# Sheet2.net
KiCad netlist of a schematic drawn in Altium Designer
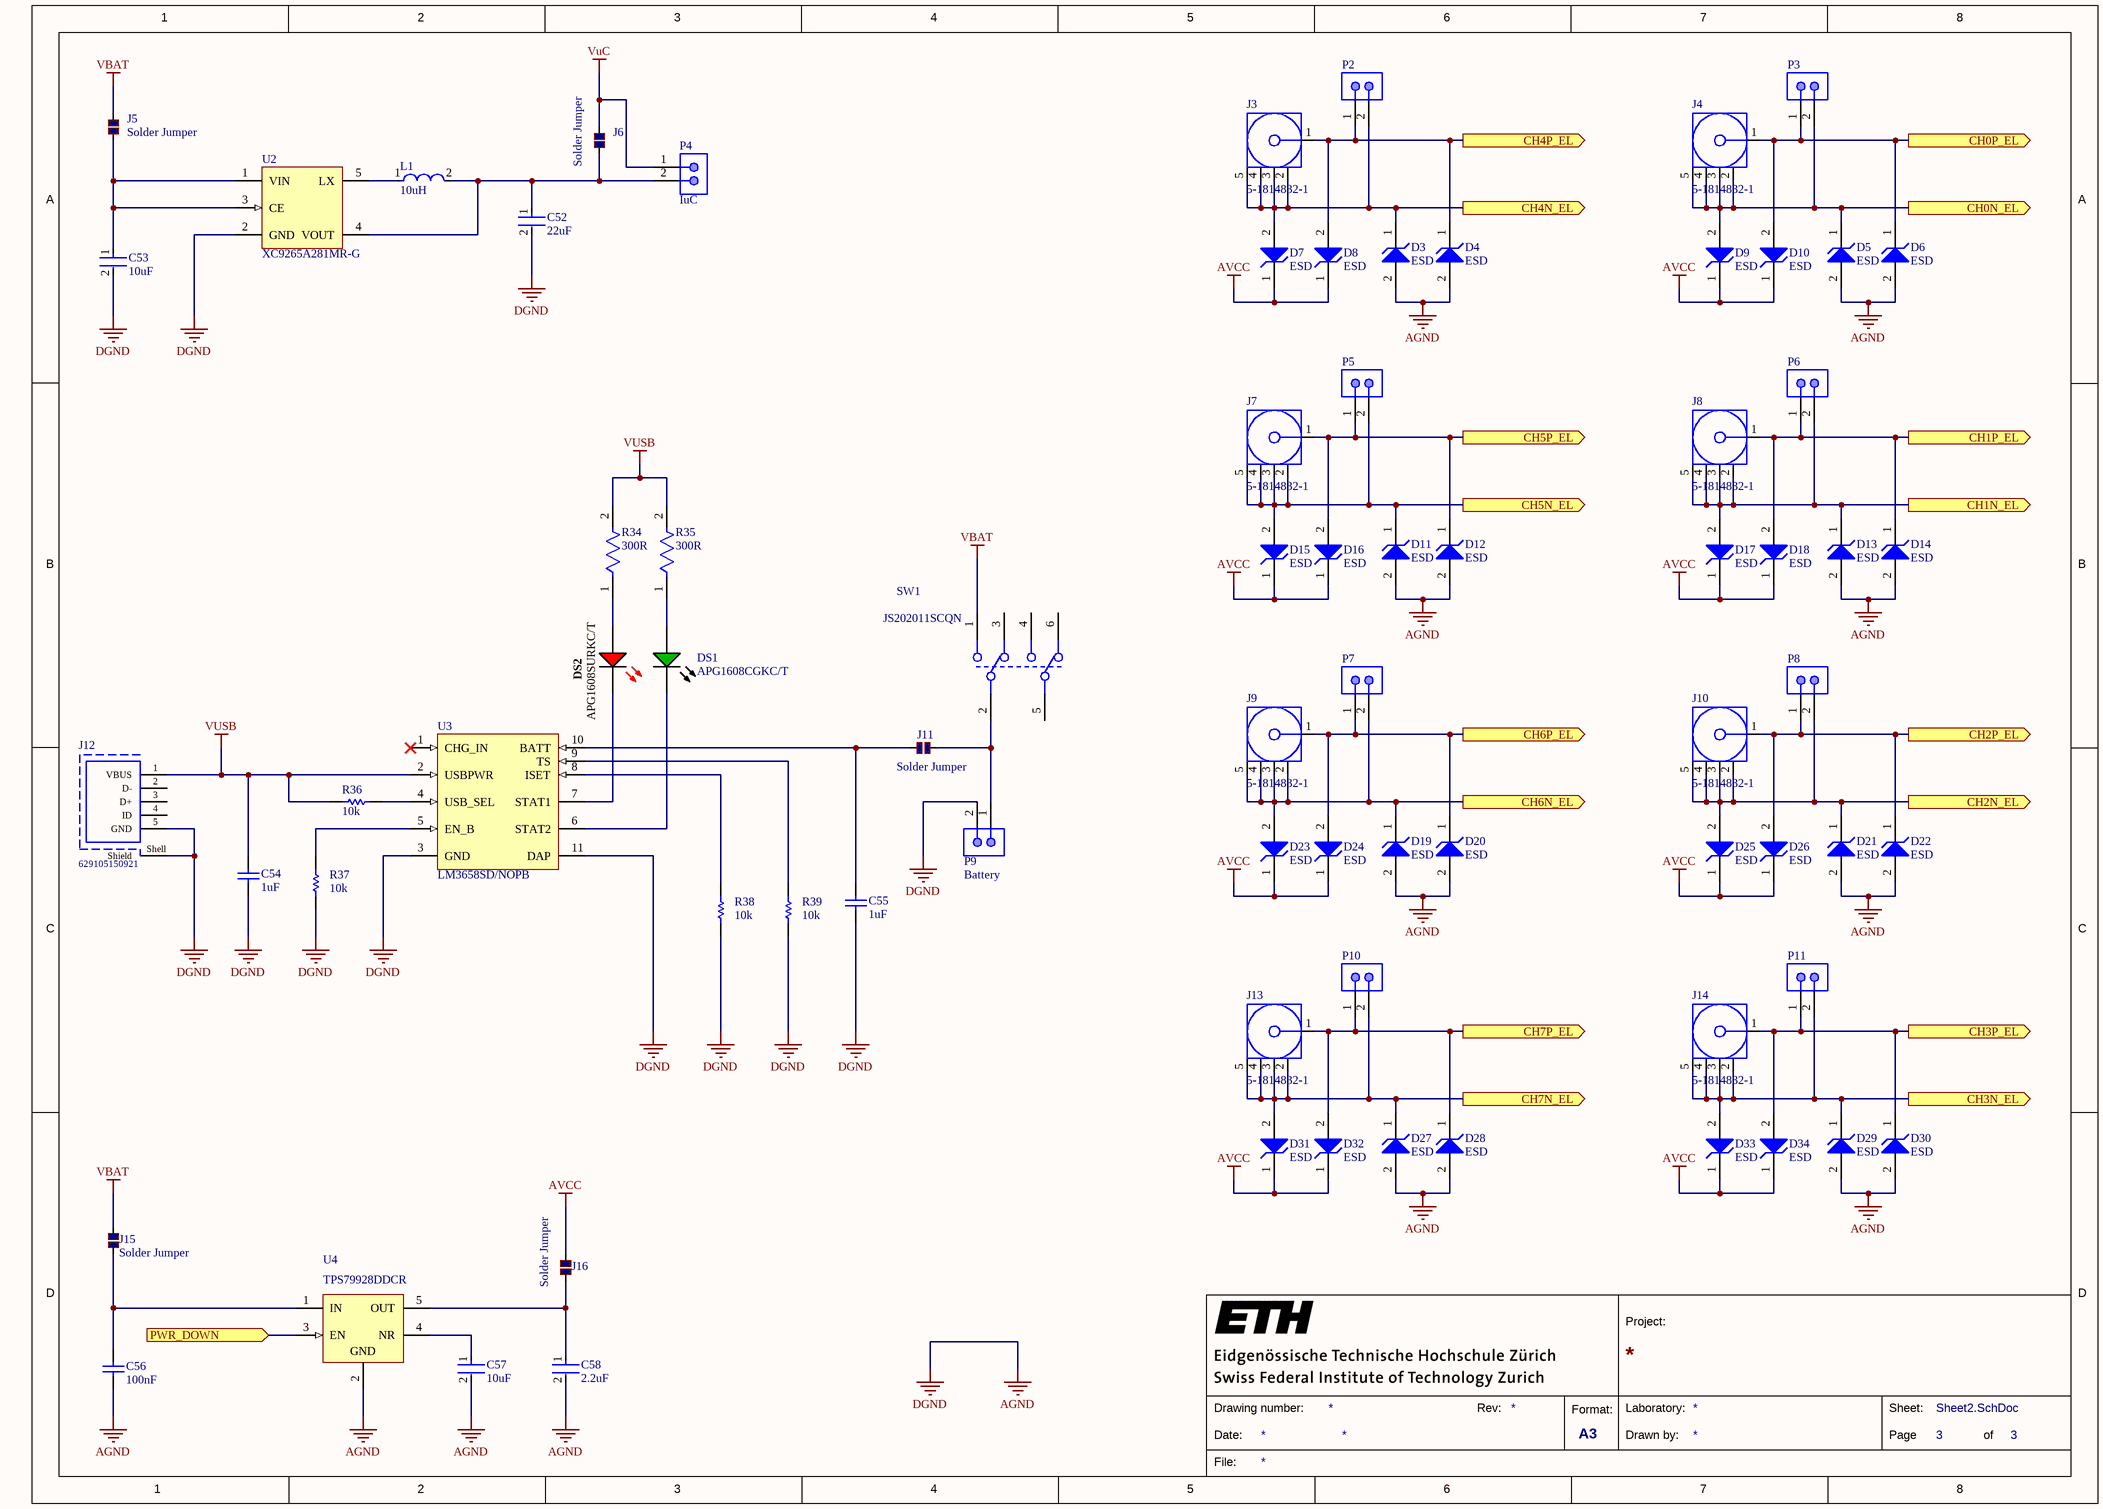
[diagram p0: Sheet2.SchDoc]

(export (version "E")
  (design (tool "Eeschema 10.0.6"))
  (components
    (comp (ref "C52")
      (value "22uF")
      (footprint "FP-CL10-IPC_A")
      (description "Cap Ceramic 22uF 6.3V X5R ±20% Pad SMD 0603 +85°C T/R")
      (fields (field (name "TOLERANCE") "20%"))
      (libsource (lib "Altium Content Vault") (part "b4654b650e69147ec39a6b967a45e02"))
    )
    (comp (ref "C53")
      (value "10uF")
      (footprint "FP-GRM188-0_1-e0_2_0_55-IPC_B")
      (description "Chip Multilayer Ceramic Capacitors for General Purpose, 0603, 10uF, X5R, 15%, 20%, 4V")
      (fields (field (name "TOLERANCE") "20%") (field (name "VOLTAGE") "4V"))
      (libsource (lib "Altium Content Vault") (part "02cd4be3c70576c341d710602a673aa"))
    )
    (comp (ref "C54")
      (value "1uF")
      (footprint "CAPC1608X95X40ML15T15")
      (fields (field (name "MANUFACTURER") "Vitramon") (field (name "PART NUMBER") "VJ0603V105ZXQCW1BC"))
      (libsource (lib "Altium Content Vault") (part "CAP"))
    )
    (comp (ref "C55")
      (value "1uF")
      (footprint "CAPC1608X95X40ML15T15")
      (fields (field (name "MANUFACTURER") "Vitramon") (field (name "PART NUMBER") "VJ0603V105ZXQCW1BC"))
      (libsource (lib "Altium Content Vault") (part "CAP"))
    )
    (comp (ref "C56")
      (value "100nF")
      (footprint "CAPC1608X92X38LL15T08")
      (fields (field (name "MANUFACTURER") "Vitramon") (field (name "PART NUMBER") "VJ0603Y104JXJAC"))
      (libsource (lib "Altium Content Vault") (part "CAP"))
    )
    (comp (ref "C57")
      (value "10uF")
      (footprint "FP-GRM188-0_1-e0_2_0_55-IPC_B")
      (description "Chip Multilayer Ceramic Capacitors for General Purpose, 0603, 10uF, X5R, 15%, 20%, 4V")
      (fields (field (name "TOLERANCE") "20%") (field (name "VOLTAGE") "4V"))
      (libsource (lib "Altium Content Vault") (part "02cd4be3c70576c341d710602a673aa"))
    )
    (comp (ref "C58")
      (value "2.2uF")
      (footprint "FP-GRM188-0_1-e0_2_0_5-IPC_C")
      (description "Chip Multilayer Ceramic Capacitors for General Purpose, 0603, 2.2uF, X5R, 15%, 10%, 35V")
      (fields (field (name "VOLTAGE") "35V") (field (name "TOLERANCE") "10%"))
      (libsource (lib "Altium Content Vault") (part "11868f565c42a9108669ba33697ecf6"))
    )
    (comp (ref "D3")
      (value "ESD")
      (footprint "DFN110P160X55-2N")
      (description "TVS DIODE 5V 10.9V 2DFN")
      (libsource (lib "ETHZ Vault") (part "TVS DIODE"))
    )
    (comp (ref "D4")
      (value "ESD")
      (footprint "DFN110P160X55-2N")
      (description "TVS DIODE 5V 10.9V 2DFN")
      (libsource (lib "ETHZ Vault") (part "TVS DIODE"))
    )
    (comp (ref "D5")
      (value "ESD")
      (footprint "DFN110P160X55-2N")
      (description "TVS DIODE 5V 10.9V 2DFN")
      (libsource (lib "ETHZ Vault") (part "TVS DIODE"))
    )
    (comp (ref "D6")
      (value "ESD")
      (footprint "DFN110P160X55-2N")
      (description "TVS DIODE 5V 10.9V 2DFN")
      (libsource (lib "ETHZ Vault") (part "TVS DIODE"))
    )
    (comp (ref "D7")
      (value "ESD")
      (footprint "DFN110P160X55-2N")
      (description "TVS DIODE 5V 10.9V 2DFN")
      (libsource (lib "ETHZ Vault") (part "TVS DIODE"))
    )
    (comp (ref "D8")
      (value "ESD")
      (footprint "DFN110P160X55-2N")
      (description "TVS DIODE 5V 10.9V 2DFN")
      (libsource (lib "ETHZ Vault") (part "TVS DIODE"))
    )
    (comp (ref "D9")
      (value "ESD")
      (footprint "DFN110P160X55-2N")
      (description "TVS DIODE 5V 10.9V 2DFN")
      (libsource (lib "ETHZ Vault") (part "TVS DIODE"))
    )
    (comp (ref "D10")
      (value "ESD")
      (footprint "DFN110P160X55-2N")
      (description "TVS DIODE 5V 10.9V 2DFN")
      (libsource (lib "ETHZ Vault") (part "TVS DIODE"))
    )
    (comp (ref "D11")
      (value "ESD")
      (footprint "DFN110P160X55-2N")
      (description "TVS DIODE 5V 10.9V 2DFN")
      (libsource (lib "ETHZ Vault") (part "TVS DIODE"))
    )
    (comp (ref "D12")
      (value "ESD")
      (footprint "DFN110P160X55-2N")
      (description "TVS DIODE 5V 10.9V 2DFN")
      (libsource (lib "ETHZ Vault") (part "TVS DIODE"))
    )
    (comp (ref "D13")
      (value "ESD")
      (footprint "DFN110P160X55-2N")
      (description "TVS DIODE 5V 10.9V 2DFN")
      (libsource (lib "ETHZ Vault") (part "TVS DIODE"))
    )
    (comp (ref "D14")
      (value "ESD")
      (footprint "DFN110P160X55-2N")
      (description "TVS DIODE 5V 10.9V 2DFN")
      (libsource (lib "ETHZ Vault") (part "TVS DIODE"))
    )
    (comp (ref "D15")
      (value "ESD")
      (footprint "DFN110P160X55-2N")
      (description "TVS DIODE 5V 10.9V 2DFN")
      (libsource (lib "ETHZ Vault") (part "TVS DIODE"))
    )
    (comp (ref "D16")
      (value "ESD")
      (footprint "DFN110P160X55-2N")
      (description "TVS DIODE 5V 10.9V 2DFN")
      (libsource (lib "ETHZ Vault") (part "TVS DIODE"))
    )
    (comp (ref "D17")
      (value "ESD")
      (footprint "DFN110P160X55-2N")
      (description "TVS DIODE 5V 10.9V 2DFN")
      (libsource (lib "ETHZ Vault") (part "TVS DIODE"))
    )
    (comp (ref "D18")
      (value "ESD")
      (footprint "DFN110P160X55-2N")
      (description "TVS DIODE 5V 10.9V 2DFN")
      (libsource (lib "ETHZ Vault") (part "TVS DIODE"))
    )
    (comp (ref "D19")
      (value "ESD")
      (footprint "DFN110P160X55-2N")
      (description "TVS DIODE 5V 10.9V 2DFN")
      (libsource (lib "ETHZ Vault") (part "TVS DIODE"))
    )
    (comp (ref "D20")
      (value "ESD")
      (footprint "DFN110P160X55-2N")
      (description "TVS DIODE 5V 10.9V 2DFN")
      (libsource (lib "ETHZ Vault") (part "TVS DIODE"))
    )
    (comp (ref "D21")
      (value "ESD")
      (footprint "DFN110P160X55-2N")
      (description "TVS DIODE 5V 10.9V 2DFN")
      (libsource (lib "ETHZ Vault") (part "TVS DIODE"))
    )
    (comp (ref "D22")
      (value "ESD")
      (footprint "DFN110P160X55-2N")
      (description "TVS DIODE 5V 10.9V 2DFN")
      (libsource (lib "ETHZ Vault") (part "TVS DIODE"))
    )
    (comp (ref "D23")
      (value "ESD")
      (footprint "DFN110P160X55-2N")
      (description "TVS DIODE 5V 10.9V 2DFN")
      (libsource (lib "ETHZ Vault") (part "TVS DIODE"))
    )
    (comp (ref "D24")
      (value "ESD")
      (footprint "DFN110P160X55-2N")
      (description "TVS DIODE 5V 10.9V 2DFN")
      (libsource (lib "ETHZ Vault") (part "TVS DIODE"))
    )
    (comp (ref "D25")
      (value "ESD")
      (footprint "DFN110P160X55-2N")
      (description "TVS DIODE 5V 10.9V 2DFN")
      (libsource (lib "ETHZ Vault") (part "TVS DIODE"))
    )
    (comp (ref "D26")
      (value "ESD")
      (footprint "DFN110P160X55-2N")
      (description "TVS DIODE 5V 10.9V 2DFN")
      (libsource (lib "ETHZ Vault") (part "TVS DIODE"))
    )
    (comp (ref "D27")
      (value "ESD")
      (footprint "DFN110P160X55-2N")
      (description "TVS DIODE 5V 10.9V 2DFN")
      (libsource (lib "ETHZ Vault") (part "TVS DIODE"))
    )
    (comp (ref "D28")
      (value "ESD")
      (footprint "DFN110P160X55-2N")
      (description "TVS DIODE 5V 10.9V 2DFN")
      (libsource (lib "ETHZ Vault") (part "TVS DIODE"))
    )
    (comp (ref "D29")
      (value "ESD")
      (footprint "DFN110P160X55-2N")
      (description "TVS DIODE 5V 10.9V 2DFN")
      (libsource (lib "ETHZ Vault") (part "TVS DIODE"))
    )
    (comp (ref "D30")
      (value "ESD")
      (footprint "DFN110P160X55-2N")
      (description "TVS DIODE 5V 10.9V 2DFN")
      (libsource (lib "ETHZ Vault") (part "TVS DIODE"))
    )
    (comp (ref "D31")
      (value "ESD")
      (footprint "DFN110P160X55-2N")
      (description "TVS DIODE 5V 10.9V 2DFN")
      (libsource (lib "ETHZ Vault") (part "TVS DIODE"))
    )
    (comp (ref "D32")
      (value "ESD")
      (footprint "DFN110P160X55-2N")
      (description "TVS DIODE 5V 10.9V 2DFN")
      (libsource (lib "ETHZ Vault") (part "TVS DIODE"))
    )
    (comp (ref "D33")
      (value "ESD")
      (footprint "DFN110P160X55-2N")
      (description "TVS DIODE 5V 10.9V 2DFN")
      (libsource (lib "ETHZ Vault") (part "TVS DIODE"))
    )
    (comp (ref "D34")
      (value "ESD")
      (footprint "DFN110P160X55-2N")
      (description "TVS DIODE 5V 10.9V 2DFN")
      (libsource (lib "ETHZ Vault") (part "TVS DIODE"))
    )
    (comp (ref "DS1")
      (value "APG1608CGKC/T")
      (footprint "KING-LED0603-25-GREEN_V")
      (description "LED, SMT, 0603(1608), 0.25mm Thickness, Green")
      (libsource (lib "Altium Content Vault") (part "KING-LED_GREEN_A1K2-2"))
    )
    (comp (ref "DS2")
      (value "APG1608SURKC/T")
      (footprint "KING-LED0603-25-RED_V")
      (fields (field (name "MANUFACTURER") "Kingbright"))
      (libsource (lib "Altium Content Vault") (part "KING-LED_RED_A1K2-2"))
    )
    (comp (ref "J3")
      (value "5-1814832-1")
      (footprint "TECO-5-1814832-1_V")
      (fields (field (name "MANUFACTURER") "TE Connectivity"))
      (libsource (lib "Altium Content Vault") (part "CN-S-4F-RF5"))
    )
    (comp (ref "J4")
      (value "5-1814832-1")
      (footprint "TECO-5-1814832-1_V")
      (fields (field (name "MANUFACTURER") "TE Connectivity"))
      (libsource (lib "Altium Content Vault") (part "CN-S-4F-RF5"))
    )
    (comp (ref "J5")
      (value "Solder Jumper")
      (footprint "Small Solder Jumper")
      (libsource (lib "ETHZ Vault") (part "Solder Jumper"))
    )
    (comp (ref "J6")
      (value "Solder Jumper")
      (footprint "Small Solder Jumper")
      (libsource (lib "ETHZ Vault") (part "Solder Jumper"))
    )
    (comp (ref "J7")
      (value "5-1814832-1")
      (footprint "TECO-5-1814832-1_V")
      (fields (field (name "MANUFACTURER") "TE Connectivity"))
      (libsource (lib "Altium Content Vault") (part "CN-S-4F-RF5"))
    )
    (comp (ref "J8")
      (value "5-1814832-1")
      (footprint "TECO-5-1814832-1_V")
      (fields (field (name "MANUFACTURER") "TE Connectivity"))
      (libsource (lib "Altium Content Vault") (part "CN-S-4F-RF5"))
    )
    (comp (ref "J9")
      (value "5-1814832-1")
      (footprint "TECO-5-1814832-1_V")
      (fields (field (name "MANUFACTURER") "TE Connectivity"))
      (libsource (lib "Altium Content Vault") (part "CN-S-4F-RF5"))
    )
    (comp (ref "J10")
      (value "5-1814832-1")
      (footprint "TECO-5-1814832-1_V")
      (fields (field (name "MANUFACTURER") "TE Connectivity"))
      (libsource (lib "Altium Content Vault") (part "CN-S-4F-RF5"))
    )
    (comp (ref "J11")
      (value "Solder Jumper")
      (footprint "Small Solder Jumper")
      (libsource (lib "") (part "Solder Jumper_1"))
    )
    (comp (ref "J12")
      (value "629105150921")
      (footprint "629105150921")
      (description "Micro USB 2.0 Type AB Receptacle WR-COM, Horizontal, SMT")
      (fields (field (name "MANUFACTURER") "Wurth Elektronik") (field (name "PUBLISHER") "WurthElektronik"))
      (libsource (lib "Altium Content Vault") (part "WE-USB-5-1SHLD"))
    )
    (comp (ref "J13")
      (value "5-1814832-1")
      (footprint "TECO-5-1814832-1_V")
      (fields (field (name "MANUFACTURER") "TE Connectivity"))
      (libsource (lib "Altium Content Vault") (part "CN-S-4F-RF5"))
    )
    (comp (ref "J14")
      (value "5-1814832-1")
      (footprint "TECO-5-1814832-1_V")
      (fields (field (name "MANUFACTURER") "TE Connectivity"))
      (libsource (lib "Altium Content Vault") (part "CN-S-4F-RF5"))
    )
    (comp (ref "J15")
      (value "Solder Jumper")
      (footprint "Small Solder Jumper")
      (libsource (lib "") (part "Solder Jumper_2"))
    )
    (comp (ref "J16")
      (value "Solder Jumper")
      (footprint "Small Solder Jumper")
      (libsource (lib "") (part "Solder Jumper_2"))
    )
    (comp (ref "L1")
      (value "10uH")
      (footprint "FP-LQH43CN_03-MFG")
      (description "Wire Wound Ferrite Inductor for Power Lines 10μH ±20% 0.1764Ω 1170mA 1812")
      (fields (field (name "TOLERANCE") "20%"))
      (libsource (lib "Altium Content Vault") (part "725321dda6339637d4d059423bc1c3c"))
    )
    (comp (ref "P2")
      (value "FIX_RLD")
      (footprint "SMTC-TSW-102-07-S-S")
      (fields (field (name "MANUFACTURER") "Samtec"))
      (libsource (lib "Altium Content Vault") (part "CN-1P-M-R2"))
    )
    (comp (ref "P3")
      (value "FIX_RLD")
      (footprint "SMTC-TSW-102-07-S-S")
      (fields (field (name "MANUFACTURER") "Samtec"))
      (libsource (lib "Altium Content Vault") (part "CN-1P-M-R2"))
    )
    (comp (ref "P4")
      (value "IuC")
      (footprint "SMTC-TSW-102-07-S-S")
      (fields (field (name "MANUFACTURER") "Samtec"))
      (libsource (lib "") (part "CN-1P-M-R2_2"))
    )
    (comp (ref "P5")
      (value "FIX_RLD")
      (footprint "SMTC-TSW-102-07-S-S")
      (fields (field (name "MANUFACTURER") "Samtec"))
      (libsource (lib "Altium Content Vault") (part "CN-1P-M-R2"))
    )
    (comp (ref "P6")
      (value "FIX_RLD")
      (footprint "SMTC-TSW-102-07-S-S")
      (fields (field (name "MANUFACTURER") "Samtec"))
      (libsource (lib "Altium Content Vault") (part "CN-1P-M-R2"))
    )
    (comp (ref "P7")
      (value "FIX_RLD")
      (footprint "SMTC-TSW-102-07-S-S")
      (fields (field (name "MANUFACTURER") "Samtec"))
      (libsource (lib "Altium Content Vault") (part "CN-1P-M-R2"))
    )
    (comp (ref "P8")
      (value "FIX_RLD")
      (footprint "SMTC-TSW-102-07-S-S")
      (fields (field (name "MANUFACTURER") "Samtec"))
      (libsource (lib "Altium Content Vault") (part "CN-1P-M-R2"))
    )
    (comp (ref "P9")
      (value "Battery")
      (footprint "SMTC-TSW-102-07-S-S")
      (fields (field (name "MANUFACTURER") "Samtec"))
      (libsource (lib "") (part "CN-1P-M-R2_1"))
    )
    (comp (ref "P10")
      (value "FIX_RLD")
      (footprint "SMTC-TSW-102-07-S-S")
      (fields (field (name "MANUFACTURER") "Samtec"))
      (libsource (lib "Altium Content Vault") (part "CN-1P-M-R2"))
    )
    (comp (ref "P11")
      (value "FIX_RLD")
      (footprint "SMTC-TSW-102-07-S-S")
      (fields (field (name "MANUFACTURER") "Samtec"))
      (libsource (lib "Altium Content Vault") (part "CN-1P-M-R2"))
    )
    (comp (ref "R34")
      (value "300R")
      (footprint "FP-CRCW0603-e3-IPC_A")
      (description "RES Thick Film, 300Ω, 1%, 0.1W, 100ppm/°C, 0603")
      (fields (field (name "TOLERANCE") "1%"))
      (libsource (lib "Altium Content Vault") (part "1029c3af85768c4190bb7ad29bc67b5"))
    )
    (comp (ref "R35")
      (value "300R")
      (footprint "FP-CRCW0603-e3-IPC_A")
      (description "RES Thick Film, 300Ω, 1%, 0.1W, 100ppm/°C, 0603")
      (fields (field (name "TOLERANCE") "1%"))
      (libsource (lib "Altium Content Vault") (part "1029c3af85768c4190bb7ad29bc67b5"))
    )
    (comp (ref "R36")
      (value "10k")
      (footprint "RESC1609X50X30NL8T20")
      (description "Chip Resistor, 10 KOhm, +/- 1%, 100 mW, -55 to 155 degC, 0603 (1608 Metric), RoHS, Tape and Reel")
      (fields (field (name "MANUFACTURER") "Vishay Semiconductor"))
      (libsource (lib "Altium Content Vault") (part "RES-2"))
    )
    (comp (ref "R37")
      (value "10k")
      (footprint "RESC1609X50X30NL8T20")
      (description "Chip Resistor, 10 KOhm, +/- 1%, 100 mW, -55 to 155 degC, 0603 (1608 Metric), RoHS, Tape and Reel")
      (fields (field (name "MANUFACTURER") "Vishay Semiconductor"))
      (libsource (lib "Altium Content Vault") (part "RES-2"))
    )
    (comp (ref "R38")
      (value "10k")
      (footprint "RESC1609X50X30NL8T20")
      (description "Chip Resistor, 10 KOhm, +/- 1%, 100 mW, -55 to 155 degC, 0603 (1608 Metric), RoHS, Tape and Reel")
      (fields (field (name "MANUFACTURER") "Vishay Semiconductor"))
      (libsource (lib "Altium Content Vault") (part "RES-2"))
    )
    (comp (ref "R39")
      (value "10k")
      (footprint "RESC1609X50X30NL8T20")
      (description "Chip Resistor, 10 KOhm, +/- 1%, 100 mW, -55 to 155 degC, 0603 (1608 Metric), RoHS, Tape and Reel")
      (fields (field (name "MANUFACTURER") "Vishay Semiconductor"))
      (libsource (lib "Altium Content Vault") (part "RES-2"))
    )
    (comp (ref "SW1")
      (value "JS202011SCQN")
      (footprint "FP-JS202011SCQN-MFG")
      (description "SWITCH SLIDE DPDT 300MA 6V")
      (libsource (lib "Altium Content Vault") (part "ac99ea1af431c19115f5225061c5c88"))
    )
    (comp (ref "U2")
      (value "XC9265A281MR-G")
      (footprint "Z5+1_N")
      (description "IC REG BUCK 1.8V 0.2A SYNC SOT25")
      (libsource (lib "ETHZ Vault") (part "XC9265"))
    )
    (comp (ref "U3")
      (value "LM3658SD/NOPB")
      (footprint "DSC0010A_V")
      (description "Dual Source USB/AC Li Chemistry Charger IC for Portable Applications, 10-pin LLP, Pb-Free")
      (fields (field (name "MANUFACTURER") "Texas Instruments"))
      (libsource (lib "Altium Content Vault") (part "PM-BCHG-LM3658SD-11"))
    )
    (comp (ref "U4")
      (value "TPS79928DDCR")
      (footprint "DDC0005A_L")
      (fields (field (name "MANUFACTURER") "Texas Instruments"))
      (libsource (lib "Altium Content Vault") (part "TI-TPS79NXX-YYSOT5"))
    )
  )
  (nets
    (net (code "1") (name "/CH0N_EL") (class "Default")
      (node (ref "D5") (pin "1") (pinfunction "1_1") (pintype "passive"))
      (node (ref "D9") (pin "2") (pinfunction "2_2") (pintype "passive"))
      (node (ref "J4") (pin "2") (pinfunction "2_2") (pintype "passive"))
      (node (ref "J4") (pin "3") (pinfunction "3_3") (pintype "passive"))
      (node (ref "J4") (pin "4") (pinfunction "4_4") (pintype "passive"))
      (node (ref "J4") (pin "5") (pinfunction "5_5") (pintype "passive"))
      (node (ref "P3") (pin "2") (pinfunction "2_2") (pintype "passive"))
    )
    (net (code "2") (name "/CH0P_EL") (class "Default")
      (node (ref "D10") (pin "2") (pinfunction "2_2") (pintype "passive"))
      (node (ref "D6") (pin "1") (pinfunction "1_1") (pintype "passive"))
      (node (ref "J4") (pin "1") (pinfunction "1_1") (pintype "passive"))
      (node (ref "P3") (pin "1") (pinfunction "1_1") (pintype "passive"))
    )
    (net (code "3") (name "/CH1N_EL") (class "Default")
      (node (ref "D13") (pin "1") (pinfunction "1_1") (pintype "passive"))
      (node (ref "D17") (pin "2") (pinfunction "2_2") (pintype "passive"))
      (node (ref "J8") (pin "2") (pinfunction "2_2") (pintype "passive"))
      (node (ref "J8") (pin "3") (pinfunction "3_3") (pintype "passive"))
      (node (ref "J8") (pin "4") (pinfunction "4_4") (pintype "passive"))
      (node (ref "J8") (pin "5") (pinfunction "5_5") (pintype "passive"))
      (node (ref "P6") (pin "2") (pinfunction "2_2") (pintype "passive"))
    )
    (net (code "4") (name "/CH1P_EL") (class "Default")
      (node (ref "D14") (pin "1") (pinfunction "1_1") (pintype "passive"))
      (node (ref "D18") (pin "2") (pinfunction "2_2") (pintype "passive"))
      (node (ref "J8") (pin "1") (pinfunction "1_1") (pintype "passive"))
      (node (ref "P6") (pin "1") (pinfunction "1_1") (pintype "passive"))
    )
    (net (code "5") (name "/CH2N_EL") (class "Default")
      (node (ref "D21") (pin "1") (pinfunction "1_1") (pintype "passive"))
      (node (ref "D25") (pin "2") (pinfunction "2_2") (pintype "passive"))
      (node (ref "J10") (pin "2") (pinfunction "2_2") (pintype "passive"))
      (node (ref "J10") (pin "3") (pinfunction "3_3") (pintype "passive"))
      (node (ref "J10") (pin "4") (pinfunction "4_4") (pintype "passive"))
      (node (ref "J10") (pin "5") (pinfunction "5_5") (pintype "passive"))
      (node (ref "P8") (pin "2") (pinfunction "2_2") (pintype "passive"))
    )
    (net (code "6") (name "/CH2P_EL") (class "Default")
      (node (ref "D22") (pin "1") (pinfunction "1_1") (pintype "passive"))
      (node (ref "D26") (pin "2") (pinfunction "2_2") (pintype "passive"))
      (node (ref "J10") (pin "1") (pinfunction "1_1") (pintype "passive"))
      (node (ref "P8") (pin "1") (pinfunction "1_1") (pintype "passive"))
    )
    (net (code "7") (name "/CH3N_EL") (class "Default")
      (node (ref "D29") (pin "1") (pinfunction "1_1") (pintype "passive"))
      (node (ref "D33") (pin "2") (pinfunction "2_2") (pintype "passive"))
      (node (ref "J14") (pin "2") (pinfunction "2_2") (pintype "passive"))
      (node (ref "J14") (pin "3") (pinfunction "3_3") (pintype "passive"))
      (node (ref "J14") (pin "4") (pinfunction "4_4") (pintype "passive"))
      (node (ref "J14") (pin "5") (pinfunction "5_5") (pintype "passive"))
      (node (ref "P11") (pin "2") (pinfunction "2_2") (pintype "passive"))
    )
    (net (code "8") (name "/CH3P_EL") (class "Default")
      (node (ref "D30") (pin "1") (pinfunction "1_1") (pintype "passive"))
      (node (ref "D34") (pin "2") (pinfunction "2_2") (pintype "passive"))
      (node (ref "J14") (pin "1") (pinfunction "1_1") (pintype "passive"))
      (node (ref "P11") (pin "1") (pinfunction "1_1") (pintype "passive"))
    )
    (net (code "9") (name "/CH4N_EL") (class "Default")
      (node (ref "D3") (pin "1") (pinfunction "1_1") (pintype "passive"))
      (node (ref "D7") (pin "2") (pinfunction "2_2") (pintype "passive"))
      (node (ref "J3") (pin "2") (pinfunction "2_2") (pintype "passive"))
      (node (ref "J3") (pin "3") (pinfunction "3_3") (pintype "passive"))
      (node (ref "J3") (pin "4") (pinfunction "4_4") (pintype "passive"))
      (node (ref "J3") (pin "5") (pinfunction "5_5") (pintype "passive"))
      (node (ref "P2") (pin "2") (pinfunction "2_2") (pintype "passive"))
    )
    (net (code "10") (name "/CH4P_EL") (class "Default")
      (node (ref "D4") (pin "1") (pinfunction "1_1") (pintype "passive"))
      (node (ref "D8") (pin "2") (pinfunction "2_2") (pintype "passive"))
      (node (ref "J3") (pin "1") (pinfunction "1_1") (pintype "passive"))
      (node (ref "P2") (pin "1") (pinfunction "1_1") (pintype "passive"))
    )
    (net (code "11") (name "/CH5N_EL") (class "Default")
      (node (ref "D11") (pin "1") (pinfunction "1_1") (pintype "passive"))
      (node (ref "D15") (pin "2") (pinfunction "2_2") (pintype "passive"))
      (node (ref "J7") (pin "2") (pinfunction "2_2") (pintype "passive"))
      (node (ref "J7") (pin "3") (pinfunction "3_3") (pintype "passive"))
      (node (ref "J7") (pin "4") (pinfunction "4_4") (pintype "passive"))
      (node (ref "J7") (pin "5") (pinfunction "5_5") (pintype "passive"))
      (node (ref "P5") (pin "2") (pinfunction "2_2") (pintype "passive"))
    )
    (net (code "12") (name "/CH5P_EL") (class "Default")
      (node (ref "D12") (pin "1") (pinfunction "1_1") (pintype "passive"))
      (node (ref "D16") (pin "2") (pinfunction "2_2") (pintype "passive"))
      (node (ref "J7") (pin "1") (pinfunction "1_1") (pintype "passive"))
      (node (ref "P5") (pin "1") (pinfunction "1_1") (pintype "passive"))
    )
    (net (code "13") (name "/CH6N_EL") (class "Default")
      (node (ref "D19") (pin "1") (pinfunction "1_1") (pintype "passive"))
      (node (ref "D23") (pin "2") (pinfunction "2_2") (pintype "passive"))
      (node (ref "J9") (pin "2") (pinfunction "2_2") (pintype "passive"))
      (node (ref "J9") (pin "3") (pinfunction "3_3") (pintype "passive"))
      (node (ref "J9") (pin "4") (pinfunction "4_4") (pintype "passive"))
      (node (ref "J9") (pin "5") (pinfunction "5_5") (pintype "passive"))
      (node (ref "P7") (pin "2") (pinfunction "2_2") (pintype "passive"))
    )
    (net (code "14") (name "/CH6P_EL") (class "Default")
      (node (ref "D20") (pin "1") (pinfunction "1_1") (pintype "passive"))
      (node (ref "D24") (pin "2") (pinfunction "2_2") (pintype "passive"))
      (node (ref "J9") (pin "1") (pinfunction "1_1") (pintype "passive"))
      (node (ref "P7") (pin "1") (pinfunction "1_1") (pintype "passive"))
    )
    (net (code "15") (name "/CH7N_EL") (class "Default")
      (node (ref "D27") (pin "1") (pinfunction "1_1") (pintype "passive"))
      (node (ref "D31") (pin "2") (pinfunction "2_2") (pintype "passive"))
      (node (ref "J13") (pin "2") (pinfunction "2_2") (pintype "passive"))
      (node (ref "J13") (pin "3") (pinfunction "3_3") (pintype "passive"))
      (node (ref "J13") (pin "4") (pinfunction "4_4") (pintype "passive"))
      (node (ref "J13") (pin "5") (pinfunction "5_5") (pintype "passive"))
      (node (ref "P10") (pin "2") (pinfunction "2_2") (pintype "passive"))
    )
    (net (code "16") (name "/CH7P_EL") (class "Default")
      (node (ref "D28") (pin "1") (pinfunction "1_1") (pintype "passive"))
      (node (ref "D32") (pin "2") (pinfunction "2_2") (pintype "passive"))
      (node (ref "J13") (pin "1") (pinfunction "1_1") (pintype "passive"))
      (node (ref "P10") (pin "1") (pinfunction "1_1") (pintype "passive"))
    )
    (net (code "17") (name "/PWR_DOWN") (class "Default")
      (node (ref "U4") (pin "3") (pinfunction "EN_3") (pintype "input"))
    )
    (net (code "18") (name "AGND") (class "Default")
      (node (ref "C52") (pin "2") (pinfunction "2_2") (pintype "passive"))
      (node (ref "C53") (pin "2") (pinfunction "2_2") (pintype "passive"))
      (node (ref "C54") (pin "1") (pinfunction "1_1") (pintype "passive"))
      (node (ref "C55") (pin "1") (pinfunction "1_1") (pintype "passive"))
      (node (ref "C56") (pin "2") (pinfunction "2_2") (pintype "passive"))
      (node (ref "C57") (pin "2") (pinfunction "2_2") (pintype "passive"))
      (node (ref "C58") (pin "2") (pinfunction "2_2") (pintype "passive"))
      (node (ref "D11") (pin "2") (pinfunction "2_2") (pintype "passive"))
      (node (ref "D12") (pin "2") (pinfunction "2_2") (pintype "passive"))
      (node (ref "D13") (pin "2") (pinfunction "2_2") (pintype "passive"))
      (node (ref "D14") (pin "2") (pinfunction "2_2") (pintype "passive"))
      (node (ref "D19") (pin "2") (pinfunction "2_2") (pintype "passive"))
      (node (ref "D20") (pin "2") (pinfunction "2_2") (pintype "passive"))
      (node (ref "D21") (pin "2") (pinfunction "2_2") (pintype "passive"))
      (node (ref "D22") (pin "2") (pinfunction "2_2") (pintype "passive"))
      (node (ref "D27") (pin "2") (pinfunction "2_2") (pintype "passive"))
      (node (ref "D28") (pin "2") (pinfunction "2_2") (pintype "passive"))
      (node (ref "D29") (pin "2") (pinfunction "2_2") (pintype "passive"))
      (node (ref "D3") (pin "2") (pinfunction "2_2") (pintype "passive"))
      (node (ref "D30") (pin "2") (pinfunction "2_2") (pintype "passive"))
      (node (ref "D4") (pin "2") (pinfunction "2_2") (pintype "passive"))
      (node (ref "D5") (pin "2") (pinfunction "2_2") (pintype "passive"))
      (node (ref "D6") (pin "2") (pinfunction "2_2") (pintype "passive"))
      (node (ref "J12") (pin "5") (pinfunction "GND_5") (pintype "passive"))
      (node (ref "J12") (pin "Shell") (pinfunction "Shield_Shell") (pintype "passive"))
      (node (ref "P9") (pin "2") (pinfunction "2_2") (pintype "passive"))
      (node (ref "R37") (pin "1") (pinfunction "1_1") (pintype "passive"))
      (node (ref "R38") (pin "1") (pinfunction "1_1") (pintype "passive"))
      (node (ref "R39") (pin "1") (pinfunction "1_1") (pintype "passive"))
      (node (ref "U2") (pin "2") (pinfunction "GND_2") (pintype "power_in"))
      (node (ref "U3") (pin "11") (pinfunction "DAP_11") (pintype "power_in"))
      (node (ref "U3") (pin "3") (pinfunction "GND_3") (pintype "power_in"))
      (node (ref "U4") (pin "2") (pinfunction "GND_2") (pintype "power_in"))
    )
    (net (code "19") (name "AVCC") (class "Default")
      (node (ref "D10") (pin "1") (pinfunction "1_1") (pintype "passive"))
      (node (ref "D15") (pin "1") (pinfunction "1_1") (pintype "passive"))
      (node (ref "D16") (pin "1") (pinfunction "1_1") (pintype "passive"))
      (node (ref "D17") (pin "1") (pinfunction "1_1") (pintype "passive"))
      (node (ref "D18") (pin "1") (pinfunction "1_1") (pintype "passive"))
      (node (ref "D23") (pin "1") (pinfunction "1_1") (pintype "passive"))
      (node (ref "D24") (pin "1") (pinfunction "1_1") (pintype "passive"))
      (node (ref "D25") (pin "1") (pinfunction "1_1") (pintype "passive"))
      (node (ref "D26") (pin "1") (pinfunction "1_1") (pintype "passive"))
      (node (ref "D31") (pin "1") (pinfunction "1_1") (pintype "passive"))
      (node (ref "D32") (pin "1") (pinfunction "1_1") (pintype "passive"))
      (node (ref "D33") (pin "1") (pinfunction "1_1") (pintype "passive"))
      (node (ref "D34") (pin "1") (pinfunction "1_1") (pintype "passive"))
      (node (ref "D7") (pin "1") (pinfunction "1_1") (pintype "passive"))
      (node (ref "D8") (pin "1") (pinfunction "1_1") (pintype "passive"))
      (node (ref "D9") (pin "1") (pinfunction "1_1") (pintype "passive"))
      (node (ref "J16") (pin "2") (pintype "passive"))
    )
    (net (code "20") (name "Net-(DS1-A)") (class "Default")
      (node (ref "DS1") (pin "1") (pinfunction "A_1") (pintype "passive"))
      (node (ref "R35") (pin "1") (pinfunction "1_1") (pintype "passive"))
    )
    (net (code "21") (name "Net-(DS1-K)") (class "Default")
      (node (ref "DS1") (pin "2") (pinfunction "K_2") (pintype "passive"))
      (node (ref "U3") (pin "6") (pinfunction "STAT2_6") (pintype "open_collector"))
    )
    (net (code "22") (name "Net-(DS2-A)") (class "Default")
      (node (ref "DS2") (pin "1") (pinfunction "A_1") (pintype "passive"))
      (node (ref "R34") (pin "1") (pinfunction "1_1") (pintype "passive"))
    )
    (net (code "23") (name "Net-(DS2-K)") (class "Default")
      (node (ref "DS2") (pin "2") (pinfunction "K_2") (pintype "passive"))
      (node (ref "U3") (pin "7") (pinfunction "STAT1_7") (pintype "open_collector"))
    )
    (net (code "24") (name "Net-(J11-Pad1)") (class "Default")
      (node (ref "J11") (pin "1") (pintype "passive"))
      (node (ref "P9") (pin "1") (pinfunction "1_1") (pintype "passive"))
      (node (ref "SW1") (pin "2") (pinfunction "2_2") (pintype "passive"))
    )
    (net (code "25") (name "Net-(U2-CE)") (class "Default")
      (node (ref "C53") (pin "1") (pinfunction "1_1") (pintype "passive"))
      (node (ref "J5") (pin "2") (pintype "passive"))
      (node (ref "U2") (pin "1") (pinfunction "VIN_1") (pintype "power_in"))
      (node (ref "U2") (pin "3") (pinfunction "CE_3") (pintype "input"))
    )
    (net (code "26") (name "Net-(U2-LX)") (class "Default")
      (node (ref "L1") (pin "1") (pinfunction "1_1") (pintype "passive"))
      (node (ref "U2") (pin "5") (pinfunction "LX_5") (pintype "power_in"))
    )
    (net (code "27") (name "Net-(U2-VOUT)") (class "Default")
      (node (ref "C52") (pin "1") (pinfunction "1_1") (pintype "passive"))
      (node (ref "J6") (pin "2") (pintype "passive"))
      (node (ref "L1") (pin "2") (pinfunction "2_2") (pintype "passive"))
      (node (ref "P4") (pin "2") (pinfunction "2_2") (pintype "passive"))
      (node (ref "U2") (pin "4") (pinfunction "VOUT_4") (pintype "passive"))
    )
    (net (code "28") (name "Net-(U3-BATT)") (class "Default")
      (node (ref "C55") (pin "2") (pinfunction "2_2") (pintype "passive"))
      (node (ref "J11") (pin "2") (pintype "passive"))
      (node (ref "U3") (pin "10") (pinfunction "BATT_10") (pintype "input"))
    )
    (net (code "29") (name "Net-(U3-EN_B)") (class "Default")
      (node (ref "R37") (pin "2") (pinfunction "2_2") (pintype "passive"))
      (node (ref "U3") (pin "5") (pinfunction "EN_B_5") (pintype "input"))
    )
    (net (code "30") (name "Net-(U3-ISET)") (class "Default")
      (node (ref "R38") (pin "2") (pinfunction "2_2") (pintype "passive"))
      (node (ref "U3") (pin "8") (pinfunction "ISET_8") (pintype "input"))
    )
    (net (code "31") (name "Net-(U3-TS)") (class "Default")
      (node (ref "R39") (pin "2") (pinfunction "2_2") (pintype "passive"))
      (node (ref "U3") (pin "9") (pinfunction "TS_9") (pintype "input"))
    )
    (net (code "32") (name "Net-(U3-USB_SEL)") (class "Default")
      (node (ref "R36") (pin "1") (pinfunction "1_1") (pintype "passive"))
      (node (ref "U3") (pin "4") (pinfunction "USB_SEL_4") (pintype "input"))
    )
    (net (code "33") (name "Net-(U4-IN)") (class "Default")
      (node (ref "C56") (pin "1") (pinfunction "1_1") (pintype "passive"))
      (node (ref "J15") (pin "1") (pintype "passive"))
      (node (ref "U4") (pin "1") (pinfunction "IN_1") (pintype "power_in"))
    )
    (net (code "34") (name "Net-(U4-NR)") (class "Default")
      (node (ref "C57") (pin "1") (pinfunction "1_1") (pintype "passive"))
      (node (ref "U4") (pin "4") (pinfunction "NR_4") (pintype "passive"))
    )
    (net (code "35") (name "Net-(U4-OUT)") (class "Default")
      (node (ref "C58") (pin "1") (pinfunction "1_1") (pintype "passive"))
      (node (ref "J16") (pin "1") (pintype "passive"))
      (node (ref "U4") (pin "5") (pinfunction "OUT_5") (pintype "power_in"))
    )
    (net (code "36") (name "VBAT") (class "Default")
      (node (ref "J15") (pin "2") (pintype "passive"))
      (node (ref "J5") (pin "1") (pintype "passive"))
      (node (ref "SW1") (pin "1") (pinfunction "1_1") (pintype "passive"))
    )
    (net (code "37") (name "VUSB") (class "Default")
      (node (ref "C54") (pin "2") (pinfunction "2_2") (pintype "passive"))
      (node (ref "J12") (pin "1") (pinfunction "VBUS_1") (pintype "passive"))
      (node (ref "R34") (pin "2") (pinfunction "2_2") (pintype "passive"))
      (node (ref "R35") (pin "2") (pinfunction "2_2") (pintype "passive"))
      (node (ref "R36") (pin "2") (pinfunction "2_2") (pintype "passive"))
      (node (ref "U3") (pin "2") (pinfunction "USBPWR_2") (pintype "input"))
    )
    (net (code "38") (name "VuC") (class "Default")
      (node (ref "J6") (pin "1") (pintype "passive"))
      (node (ref "P4") (pin "1") (pinfunction "1_1") (pintype "passive"))
    )
    (net (code "39") (name "unconnected-(J12-D+-Pad3)") (class "Default")
      (node (ref "J12") (pin "3") (pinfunction "D+_3") (pintype "passive"))
    )
    (net (code "40") (name "unconnected-(J12-D--Pad2)") (class "Default")
      (node (ref "J12") (pin "2") (pinfunction "D-_2") (pintype "passive"))
    )
    (net (code "41") (name "unconnected-(J12-ID-Pad4)") (class "Default")
      (node (ref "J12") (pin "4") (pinfunction "ID_4") (pintype "passive"))
    )
    (net (code "42") (name "unconnected-(SW1-Pad3)") (class "Default")
      (node (ref "SW1") (pin "3") (pinfunction "3_3") (pintype "passive"))
    )
    (net (code "43") (name "unconnected-(SW1-Pad4)") (class "Default")
      (node (ref "SW1") (pin "4") (pinfunction "4_4") (pintype "passive"))
    )
    (net (code "44") (name "unconnected-(SW1-Pad5)") (class "Default")
      (node (ref "SW1") (pin "5") (pinfunction "5_5") (pintype "passive"))
    )
    (net (code "45") (name "unconnected-(SW1-Pad6)") (class "Default")
      (node (ref "SW1") (pin "6") (pinfunction "6_6") (pintype "passive"))
    )
    (net (code "46") (name "unconnected-(U3-CHG_IN-Pad1)") (class "Default")
      (node (ref "U3") (pin "1") (pinfunction "CHG_IN_1") (pintype "input+no_connect"))
    )
  )
)
